# Controller.net
KiCad netlist of a schematic drawn in Altium Designer
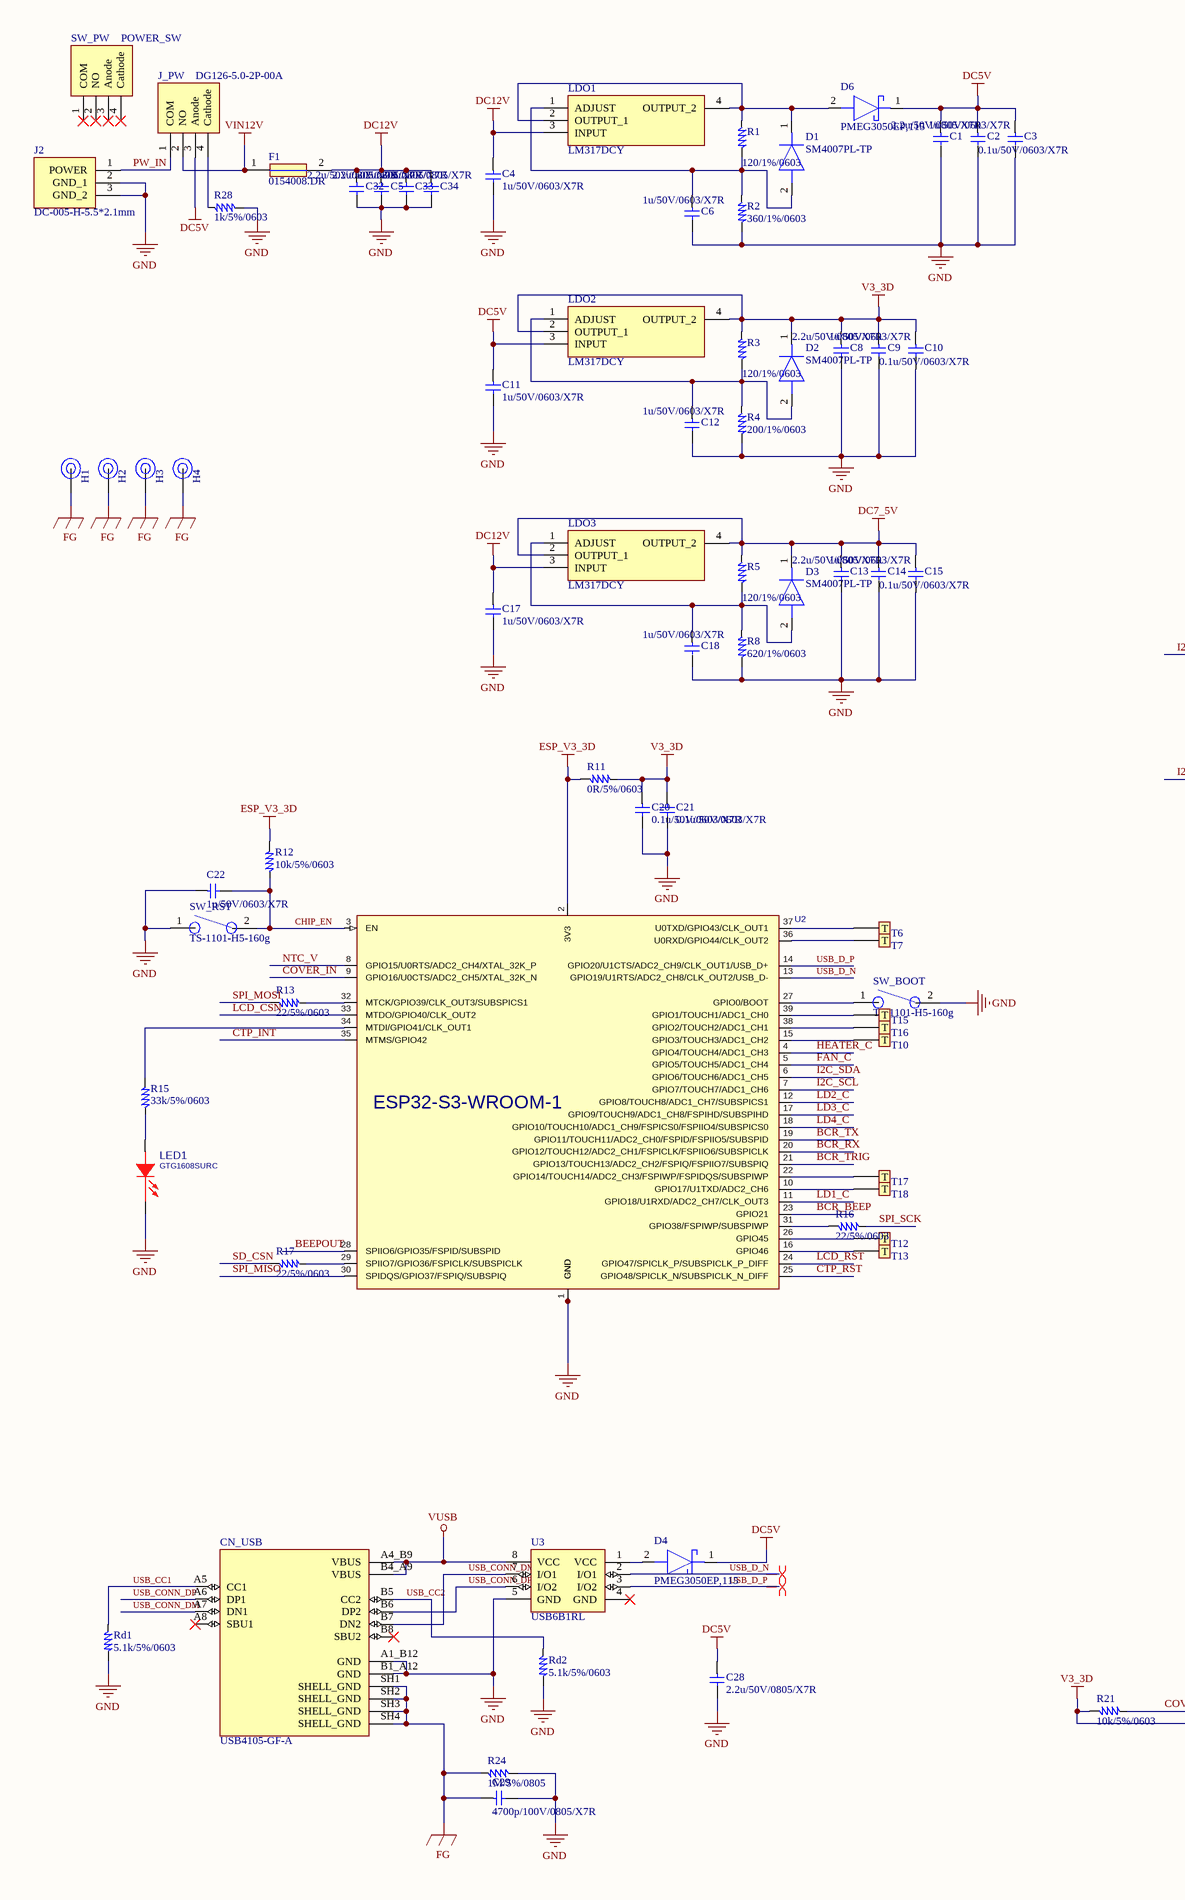
[diagram p0: Controller.SchDoc, left]
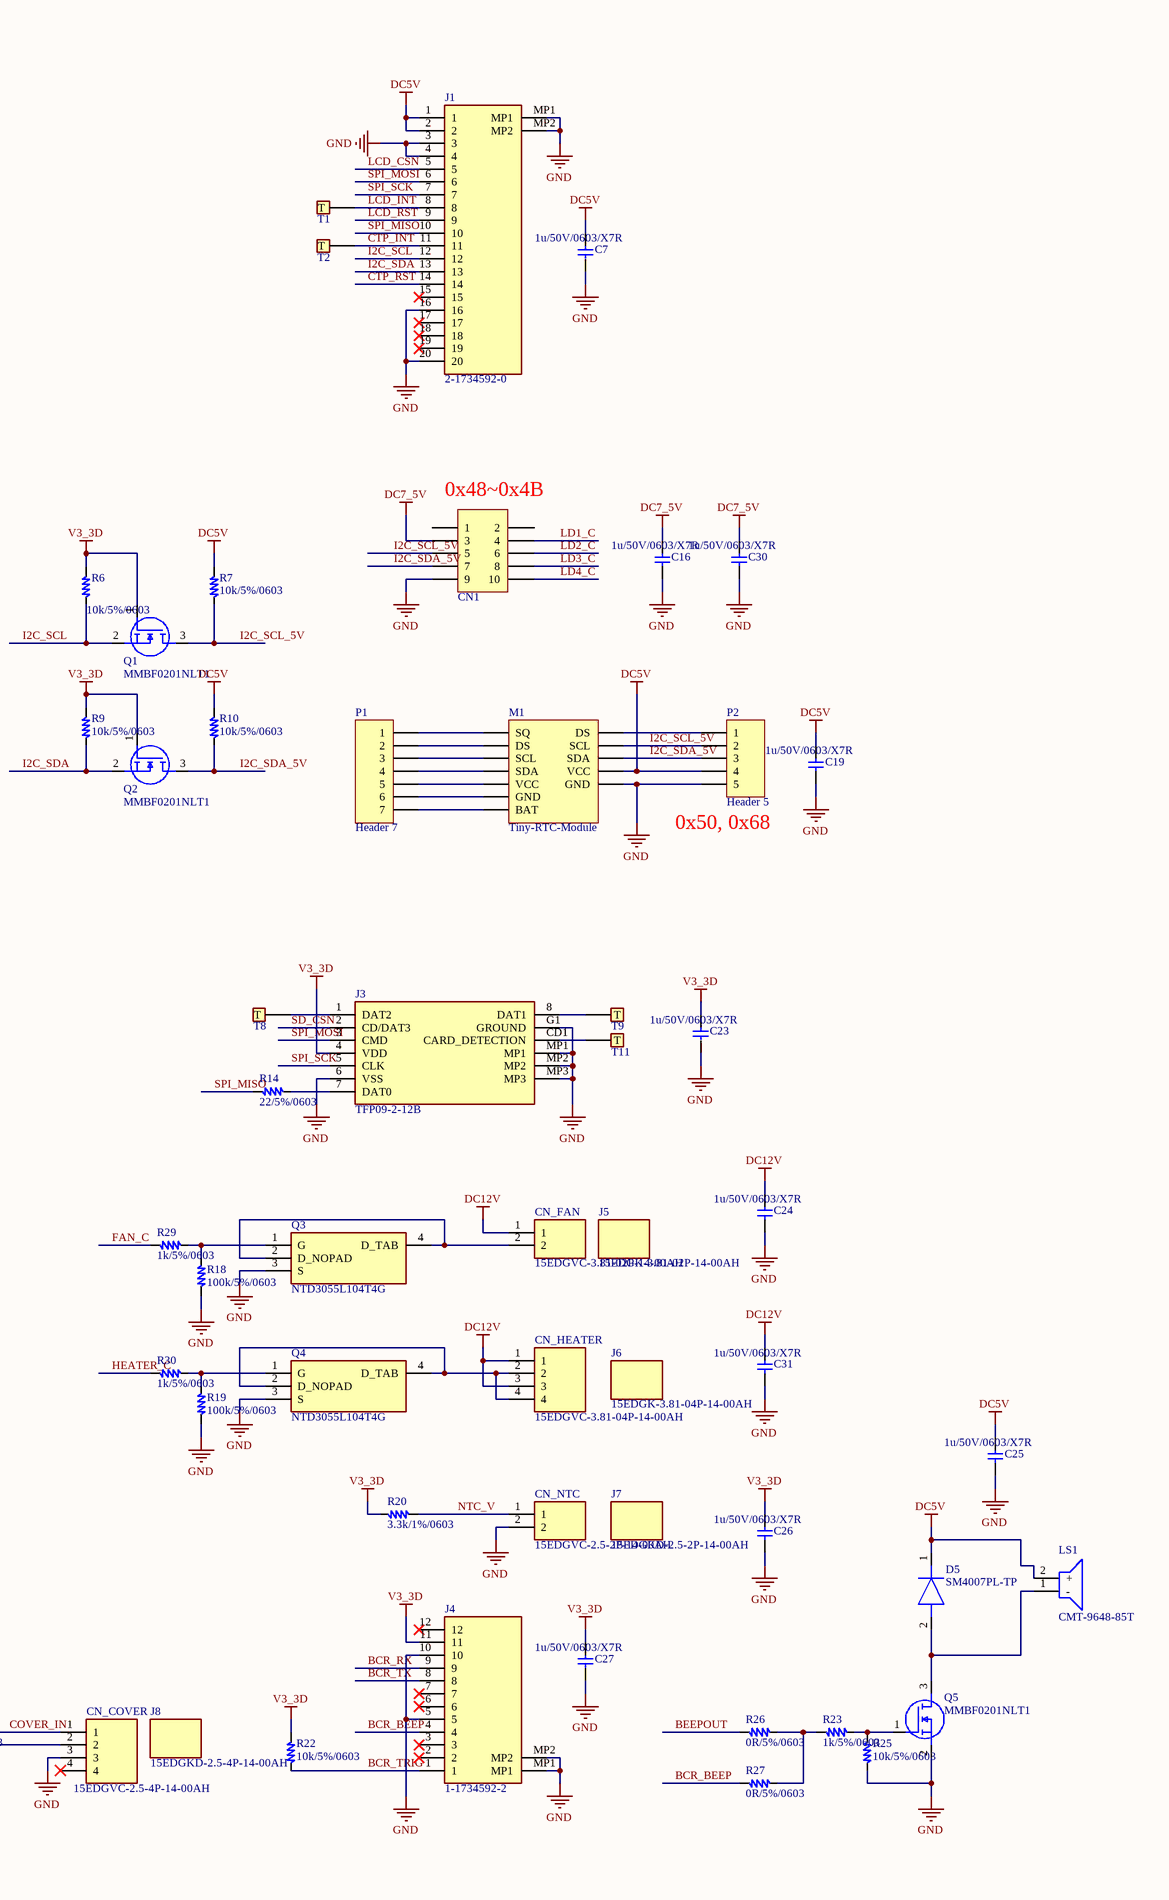
[diagram p1: Controller.SchDoc, right]

(export (version "E")
  (design (tool "Eeschema 10.0.6"))
  (components
    (comp (ref "C1")
      (value "2.2u/50V/0805/X7R")
      (footprint "CC0805")
      (description "CAP_MLCC")
      (libsource (lib "Biotaitan") (part "CAP_MLCC"))
    )
    (comp (ref "C2")
      (value "1u/50V/0603/X7R")
      (footprint "CC0603")
      (description "CAP_MLCC")
      (libsource (lib "Biotaitan") (part "CAP_MLCC"))
    )
    (comp (ref "C3")
      (value "0.1u/50V/0603/X7R")
      (footprint "CC0603")
      (description "CAP_MLCC")
      (libsource (lib "Biotaitan") (part "CAP_MLCC"))
    )
    (comp (ref "C4")
      (value "1u/50V/0603/X7R")
      (footprint "CC0603")
      (description "CAP_MLCC")
      (libsource (lib "Biotaitan") (part "CAP_MLCC"))
    )
    (comp (ref "C5")
      (value "2.2u/50V/0805/X7R")
      (footprint "CC0805")
      (description "CAP_MLCC")
      (libsource (lib "Biotaitan") (part "CAP_MLCC"))
    )
    (comp (ref "C6")
      (value "1u/50V/0603/X7R")
      (footprint "CC0603")
      (description "CAP_MLCC")
      (libsource (lib "Biotaitan") (part "CAP_MLCC"))
    )
    (comp (ref "C7")
      (value "1u/50V/0603/X7R")
      (footprint "CC0603")
      (description "CAP_MLCC")
      (libsource (lib "Biotaitan") (part "CAP_MLCC"))
    )
    (comp (ref "C8")
      (value "2.2u/50V/0805/X7R")
      (footprint "CC0805")
      (description "CAP_MLCC")
      (libsource (lib "Biotaitan") (part "CAP_MLCC"))
    )
    (comp (ref "C9")
      (value "1u/50V/0603/X7R")
      (footprint "CC0603")
      (description "CAP_MLCC")
      (libsource (lib "Biotaitan") (part "CAP_MLCC"))
    )
    (comp (ref "C10")
      (value "0.1u/50V/0603/X7R")
      (footprint "CC0603")
      (description "CAP_MLCC")
      (libsource (lib "Biotaitan") (part "CAP_MLCC"))
    )
    (comp (ref "C11")
      (value "1u/50V/0603/X7R")
      (footprint "CC0603")
      (description "CAP_MLCC")
      (libsource (lib "Biotaitan") (part "CAP_MLCC"))
    )
    (comp (ref "C12")
      (value "1u/50V/0603/X7R")
      (footprint "CC0603")
      (description "CAP_MLCC")
      (libsource (lib "Biotaitan") (part "CAP_MLCC"))
    )
    (comp (ref "C13")
      (value "2.2u/50V/0805/X7R")
      (footprint "CC0805")
      (description "CAP_MLCC")
      (libsource (lib "Biotaitan") (part "CAP_MLCC"))
    )
    (comp (ref "C14")
      (value "1u/50V/0603/X7R")
      (footprint "CC0603")
      (description "CAP_MLCC")
      (libsource (lib "Biotaitan") (part "CAP_MLCC"))
    )
    (comp (ref "C15")
      (value "0.1u/50V/0603/X7R")
      (footprint "CC0603")
      (description "CAP_MLCC")
      (libsource (lib "Biotaitan") (part "CAP_MLCC"))
    )
    (comp (ref "C16")
      (value "1u/50V/0603/X7R")
      (footprint "CC0603")
      (description "CAP_MLCC")
      (libsource (lib "Biotaitan") (part "CAP_MLCC"))
    )
    (comp (ref "C17")
      (value "1u/50V/0603/X7R")
      (footprint "CC0603")
      (description "CAP_MLCC")
      (libsource (lib "Biotaitan") (part "CAP_MLCC"))
    )
    (comp (ref "C18")
      (value "1u/50V/0603/X7R")
      (footprint "CC0603")
      (description "CAP_MLCC")
      (libsource (lib "Biotaitan") (part "CAP_MLCC"))
    )
    (comp (ref "C19")
      (value "1u/50V/0603/X7R")
      (footprint "CC0603")
      (description "CAP_MLCC")
      (libsource (lib "Biotaitan") (part "CAP_MLCC"))
    )
    (comp (ref "C20")
      (value "0.1u/50V/0603/X7R")
      (footprint "CC0603")
      (description "CAP_MLCC")
      (libsource (lib "Biotaitan") (part "CAP_MLCC"))
    )
    (comp (ref "C21")
      (value "0.1u/50V/0603/X7R")
      (footprint "CC0603")
      (description "CAP_MLCC")
      (libsource (lib "Biotaitan") (part "CAP_MLCC"))
    )
    (comp (ref "C22")
      (value "1u/50V/0603/X7R")
      (footprint "CC0603")
      (description "CAP_MLCC")
      (libsource (lib "Biotaitan") (part "CAP_MLCC"))
    )
    (comp (ref "C23")
      (value "1u/50V/0603/X7R")
      (footprint "CC0603")
      (description "CAP_MLCC")
      (libsource (lib "Biotaitan") (part "CAP_MLCC"))
    )
    (comp (ref "C24")
      (value "1u/50V/0603/X7R")
      (footprint "CC0603")
      (description "CAP_MLCC")
      (libsource (lib "Biotaitan") (part "CAP_MLCC"))
    )
    (comp (ref "C25")
      (value "1u/50V/0603/X7R")
      (footprint "CC0603")
      (description "CAP_MLCC")
      (libsource (lib "Biotaitan") (part "CAP_MLCC"))
    )
    (comp (ref "C26")
      (value "1u/50V/0603/X7R")
      (footprint "CC0603")
      (description "CAP_MLCC")
      (libsource (lib "Biotaitan") (part "CAP_MLCC"))
    )
    (comp (ref "C27")
      (value "1u/50V/0603/X7R")
      (footprint "CC0603")
      (description "CAP_MLCC")
      (libsource (lib "Biotaitan") (part "CAP_MLCC"))
    )
    (comp (ref "C28")
      (value "2.2u/50V/0805/X7R")
      (footprint "CC0805")
      (description "CAP_MLCC")
      (libsource (lib "Biotaitan") (part "CAP_MLCC"))
    )
    (comp (ref "C29")
      (value "4700p/100V/0805/X7R")
      (footprint "CC0805")
      (description "CAP_MLCC")
      (libsource (lib "Biotaitan") (part "CAP_MLCC"))
    )
    (comp (ref "C30")
      (value "1u/50V/0603/X7R")
      (footprint "CC0603")
      (description "CAP_MLCC")
      (libsource (lib "Biotaitan") (part "CAP_MLCC"))
    )
    (comp (ref "C31")
      (value "1u/50V/0603/X7R")
      (footprint "CC0603")
      (description "CAP_MLCC")
      (libsource (lib "Biotaitan") (part "CAP_MLCC"))
    )
    (comp (ref "C32")
      (value "2.2u/50V/0805/X7R")
      (footprint "CC0805")
      (description "CAP_MLCC")
      (libsource (lib "Biotaitan") (part "CAP_MLCC"))
    )
    (comp (ref "C33")
      (value "2.2u/50V/0805/X7R")
      (footprint "CC0805")
      (description "CAP_MLCC")
      (libsource (lib "Biotaitan") (part "CAP_MLCC"))
    )
    (comp (ref "C34")
      (value "2.2u/50V/0805/X7R")
      (footprint "CC0805")
      (description "CAP_MLCC")
      (libsource (lib "Biotaitan") (part "CAP_MLCC"))
    )
    (comp (ref "CN1")
      (value "320-10")
      (footprint "SHDR10W70P254_2X5_2000X850X900P")
      (description "IDC_(100y) VER TH 10POS 2.54MM")
      (libsource (lib "Biotaitan") (part "320-10"))
    )
    (comp (ref "CN_COVER")
      (value "15EDGVC-2.5-4P-14-00AH")
      (footprint "15EDGVC-2.5-4P-14-00AH")
      (description "端子台(百年)")
      (libsource (lib "Biotaitan") (part "15EDGVC-2.5-4P-14-00AH"))
    )
    (comp (ref "CN_FAN")
      (value "15EDGVC-3.81-02P-14-00AH")
      (footprint "15EDGVC-3.81-02P-14-00AH")
      (description "端子台(百年)")
      (libsource (lib "Biotaitan") (part "15EDGVC-3.81-02P-14-00AH"))
    )
    (comp (ref "CN_HEATER")
      (value "15EDGVC-3.81-04P-14-00AH")
      (footprint "15EDGVC-3.81-04P-14-00AH")
      (description "端子台(百年)")
      (libsource (lib "Biotaitan") (part "15EDGVC-3.81-04P-14-00AH"))
    )
    (comp (ref "CN_NTC")
      (value "15EDGVC-2.5-2P-14-00AH")
      (footprint "15EDGVC-2.5-2P-14-00AH")
      (description "端子台(百年)")
      (libsource (lib "Biotaitan") (part "15EDGVC-2.5-2P-14-00AH"))
    )
    (comp (ref "CN_USB")
      (value "USB4105-GF-A")
      (footprint "USB4105-GF-A")
      (description "USB_Type-C (USB2.0) 24P(16+8 Dummy)  SMD RA")
      (libsource (lib "Biotaitan") (part "USB4105-GF-A"))
    )
    (comp (ref "D1")
      (value "SM4007PL-TP")
      (footprint "SM4007PLTP")
      (description "整流器 1A, 1000V 1A, 1000V")
      (libsource (lib "Biotaitan") (part "SM4007PL-TP"))
    )
    (comp (ref "D2")
      (value "SM4007PL-TP")
      (footprint "SM4007PLTP")
      (description "整流器 1A, 1000V 1A, 1000V")
      (libsource (lib "Biotaitan") (part "SM4007PL-TP"))
    )
    (comp (ref "D3")
      (value "SM4007PL-TP")
      (footprint "SM4007PLTP")
      (description "整流器 1A, 1000V 1A, 1000V")
      (libsource (lib "Biotaitan") (part "SM4007PL-TP"))
    )
    (comp (ref "D4")
      (value "PMEG3050EP,115")
      (footprint "PMEG3050EP115")
      (description "Schottky_RECT 30V 5A VF 0.315V")
      (libsource (lib "Biotaitan") (part "PMEG3050EP,115"))
    )
    (comp (ref "D5")
      (value "SM4007PL-TP")
      (footprint "SM4007PLTP")
      (description "整流器 1A, 1000V 1A, 1000V")
      (libsource (lib "Biotaitan") (part "SM4007PL-TP"))
    )
    (comp (ref "D6")
      (value "PMEG3050EP,115")
      (footprint "PMEG3050EP115")
      (description "Schottky_RECT 30V 5A VF 0.315V")
      (libsource (lib "Biotaitan") (part "PMEG3050EP,115"))
    )
    (comp (ref "F1")
      (value "0154008.DR")
      (footprint "0154001.DRT")
      (description "Fuse")
      (libsource (lib "Biotaitan") (part "0154008.DR"))
    )
    (comp (ref "H1")
      (value "Screw_holes_3p5mm")
      (footprint "Screw_holes_3p5mm")
      (description "Screw holes")
      (libsource (lib "Biotaitan") (part "Screw_holes"))
    )
    (comp (ref "H2")
      (value "Screw_holes_3p5mm")
      (footprint "Screw_holes_3p5mm")
      (description "Screw holes")
      (libsource (lib "Biotaitan") (part "Screw_holes"))
    )
    (comp (ref "H3")
      (value "Screw_holes_3p5mm")
      (footprint "Screw_holes_3p5mm")
      (description "Screw holes")
      (libsource (lib "Biotaitan") (part "Screw_holes"))
    )
    (comp (ref "H4")
      (value "Screw_holes_3p5mm")
      (footprint "Screw_holes_3p5mm")
      (description "Screw holes")
      (libsource (lib "Biotaitan") (part "Screw_holes"))
    )
    (comp (ref "J1")
      (value "2-1734592-0")
      (footprint "217345920")
      (description "FFC和FPC連接器 0.5mm PITCH B/C 20P")
      (libsource (lib "Biotaitan") (part "2-1734592-0"))
    )
    (comp (ref "J2")
      (value "DC-005-H-5.5*2.1mm")
      (footprint "DC-005-H-5.5*2.1mm")
      (description "DC-005-H-5.5*2.1mm(百年)")
      (libsource (lib "Biotaitan") (part "DC-005-H-5.5*2.1mm"))
    )
    (comp (ref "J3")
      (value "TFP09-2-12B")
      (footprint "TFP09212B")
      (description "Micro SD Card Connector(百年)")
      (libsource (lib "Biotaitan") (part "TFP09-2-12B"))
    )
    (comp (ref "J4")
      (value "1-1734592-2")
      (footprint "117345922")
      (description "FFC和FPC連接器 0.5mm PITCH B/C 12P")
      (libsource (lib "Biotaitan") (part "1-1734592-2"))
    )
    (comp (ref "J5")
      (value "15EDGK-3.81-02P-14-00AH")
      (footprint "15EDGK-3.81-02P-14-00AH")
      (description "端子接頭(百年)")
      (libsource (lib "Biotaitan") (part "15EDGK-3.81-02P-14-00AH"))
    )
    (comp (ref "J6")
      (value "15EDGK-3.81-04P-14-00AH")
      (footprint "15EDGK-3.81-04P-14-00AH")
      (description "端子接頭(百年)")
      (libsource (lib "Biotaitan") (part "15EDGK-3.81-04P-14-00AH"))
    )
    (comp (ref "J7")
      (value "15EDGKD-2.5-2P-14-00AH")
      (footprint "15EDGKD-2.5-2P-14-00AH")
      (description "端子接頭(百年)")
      (libsource (lib "Biotaitan") (part "15EDGKD-2.5-2P-14-00AH"))
    )
    (comp (ref "J8")
      (value "15EDGKD-2.5-4P-14-00AH")
      (footprint "15EDGKD-2.5-4P-14-00AH")
      (description "端子接頭(百年)")
      (libsource (lib "Biotaitan") (part "15EDGKD-2.5-4P-14-00AH"))
    )
    (comp (ref "J_PW")
      (value "DG126-5.0-2P-00A")
      (footprint "DG126-5.0-2P-00A_PW_SW")
      (description "端子台")
      (libsource (lib "Biotaitan") (part "DG126-5.0-2P-00A_SW"))
    )
    (comp (ref "LDO1")
      (value "LM317DCY")
      (footprint "SOT230P700X180-4N")
      (description "線性電壓穩壓器 3 T 1.5A Adj Pos V")
      (libsource (lib "Biotaitan") (part "LM317DCY"))
    )
    (comp (ref "LDO2")
      (value "LM317DCY")
      (footprint "SOT230P700X180-4N")
      (description "線性電壓穩壓器 3 T 1.5A Adj Pos V")
      (libsource (lib "Biotaitan") (part "LM317DCY"))
    )
    (comp (ref "LDO3")
      (value "LM317DCY")
      (footprint "SOT230P700X180-4N")
      (description "線性電壓穩壓器 3 T 1.5A Adj Pos V")
      (libsource (lib "Biotaitan") (part "LM317DCY"))
    )
    (comp (ref "LED1")
      (value "GTG1608SURC")
      (footprint "LED0603_RED")
      (description "LED0603_RED(百年)")
      (libsource (lib "Biotaitan") (part "GTG1608SURC"))
    )
    (comp (ref "LS1")
      (value "CMT-9648-85T")
      (footprint "CMT964885T")
      (description "Loudspeaker or Buzzer")
      (libsource (lib "Biotaitan") (part "CMT-9648-85T"))
    )
    (comp (ref "M1")
      (value "Tiny-RTC-Module")
      (footprint "TINY RTC I2C Module")
      (description "DS1307 RTC Module\r\n(百年)100698")
      (libsource (lib "Biotaitan") (part "Tiny-RTC-Module"))
    )
    (comp (ref "P1")
      (value "Header 7")
      (footprint "HDR1X7_2.54_ST_H8.54")
      (description "D15-40P/全長-14.2MM(百年)")
      (libsource (lib "Biotaitan") (part "Header 7"))
    )
    (comp (ref "P2")
      (value "Header 5")
      (footprint "HDR1X5_2.54_ST_H8.54")
      (description "D15-40P/全長-14.2MM(百年)")
      (libsource (lib "Biotaitan") (part "Header 5"))
    )
    (comp (ref "Q1")
      (value "MMBF0201NLT1")
      (footprint "SOT65P210X110-3N")
      (description "MOSFET (N-Channel)(百年)")
      (libsource (lib "Biotaitan") (part "MMBF0201NLT1"))
    )
    (comp (ref "Q2")
      (value "MMBF0201NLT1")
      (footprint "SOT65P210X110-3N")
      (description "MOSFET (N-Channel)(百年)")
      (libsource (lib "Biotaitan") (part "MMBF0201NLT1"))
    )
    (comp (ref "Q3")
      (value "NTD3055L104T4G")
      (footprint "TO229P990X238-4N")
      (description "MOSFET 60V 12A N-Channel")
      (libsource (lib "Biotaitan") (part "NTD3055L104T4G"))
    )
    (comp (ref "Q4")
      (value "NTD3055L104T4G")
      (footprint "TO229P990X238-4N")
      (description "MOSFET 60V 12A N-Channel")
      (libsource (lib "Biotaitan") (part "NTD3055L104T4G"))
    )
    (comp (ref "Q5")
      (value "MMBF0201NLT1")
      (footprint "SOT65P210X110-3N")
      (description "MOSFET (N-Channel)(百年)")
      (libsource (lib "Biotaitan") (part "MMBF0201NLT1"))
    )
    (comp (ref "R1")
      (value "120/1%/0603")
      (footprint "CC0603_R")
      (description "RES_")
      (libsource (lib "Biotaitan") (part "RES_SMD"))
    )
    (comp (ref "R2")
      (value "360/1%/0603")
      (footprint "CC0603_R")
      (description "RES_")
      (libsource (lib "Biotaitan") (part "RES_SMD"))
    )
    (comp (ref "R3")
      (value "120/1%/0603")
      (footprint "CC0603_R")
      (description "RES_")
      (libsource (lib "Biotaitan") (part "RES_SMD"))
    )
    (comp (ref "R4")
      (value "200/1%/0603")
      (footprint "CC0603_R")
      (description "RES_")
      (libsource (lib "Biotaitan") (part "RES_SMD"))
    )
    (comp (ref "R5")
      (value "120/1%/0603")
      (footprint "CC0603_R")
      (description "RES_")
      (libsource (lib "Biotaitan") (part "RES_SMD"))
    )
    (comp (ref "R6")
      (value "10k/5%/0603")
      (footprint "CC0603_R")
      (description "RES_")
      (libsource (lib "Biotaitan") (part "RES_SMD"))
    )
    (comp (ref "R7")
      (value "10k/5%/0603")
      (footprint "CC0603_R")
      (description "RES_")
      (libsource (lib "Biotaitan") (part "RES_SMD"))
    )
    (comp (ref "R8")
      (value "620/1%/0603")
      (footprint "CC0603_R")
      (description "RES_")
      (libsource (lib "Biotaitan") (part "RES_SMD"))
    )
    (comp (ref "R9")
      (value "10k/5%/0603")
      (footprint "CC0603_R")
      (description "RES_")
      (libsource (lib "Biotaitan") (part "RES_SMD"))
    )
    (comp (ref "R10")
      (value "10k/5%/0603")
      (footprint "CC0603_R")
      (description "RES_")
      (libsource (lib "Biotaitan") (part "RES_SMD"))
    )
    (comp (ref "R11")
      (value "0R/5%/0603")
      (footprint "CC0603_R")
      (description "RES_")
      (libsource (lib "Biotaitan") (part "RES_SMD"))
    )
    (comp (ref "R12")
      (value "10k/5%/0603")
      (footprint "CC0603_R")
      (description "RES_")
      (libsource (lib "Biotaitan") (part "RES_SMD"))
    )
    (comp (ref "R13")
      (value "22/5%/0603")
      (footprint "CC0603_R")
      (description "RES_")
      (libsource (lib "Biotaitan") (part "RES_SMD"))
    )
    (comp (ref "R14")
      (value "22/5%/0603")
      (footprint "CC0603_R")
      (description "RES_")
      (libsource (lib "Biotaitan") (part "RES_SMD"))
    )
    (comp (ref "R15")
      (value "33k/5%/0603")
      (footprint "CC0603_R")
      (description "RES_")
      (libsource (lib "Biotaitan") (part "RES_SMD"))
    )
    (comp (ref "R16")
      (value "22/5%/0603")
      (footprint "CC0603_R")
      (description "RES_")
      (libsource (lib "Biotaitan") (part "RES_SMD"))
    )
    (comp (ref "R17")
      (value "22/5%/0603")
      (footprint "CC0603_R")
      (description "RES_")
      (libsource (lib "Biotaitan") (part "RES_SMD"))
    )
    (comp (ref "R18")
      (value "100k/5%/0603")
      (footprint "CC0603_R")
      (description "RES_")
      (libsource (lib "Biotaitan") (part "RES_SMD"))
    )
    (comp (ref "R19")
      (value "100k/5%/0603")
      (footprint "CC0603_R")
      (description "RES_")
      (libsource (lib "Biotaitan") (part "RES_SMD"))
    )
    (comp (ref "R20")
      (value "3.3k/1%/0603")
      (footprint "CC0603_R")
      (description "RES_")
      (libsource (lib "Biotaitan") (part "RES_SMD"))
    )
    (comp (ref "R21")
      (value "10k/5%/0603")
      (footprint "CC0603_R")
      (description "RES_")
      (libsource (lib "Biotaitan") (part "RES_SMD"))
    )
    (comp (ref "R22")
      (value "10k/5%/0603")
      (footprint "CC0603_R")
      (description "RES_")
      (libsource (lib "Biotaitan") (part "RES_SMD"))
    )
    (comp (ref "R23")
      (value "1k/5%/0603")
      (footprint "CC0603_R")
      (description "RES_")
      (libsource (lib "Biotaitan") (part "RES_SMD"))
    )
    (comp (ref "R24")
      (value "1M/5%/0805")
      (footprint "CC0805_R")
      (description "RES_")
      (libsource (lib "Biotaitan") (part "RES_SMD"))
    )
    (comp (ref "R25")
      (value "10k/5%/0603")
      (footprint "CC0603_R")
      (description "RES_")
      (libsource (lib "Biotaitan") (part "RES_SMD"))
    )
    (comp (ref "R26")
      (value "0R/5%/0603")
      (footprint "CC0603_R")
      (description "RES_")
      (libsource (lib "Biotaitan") (part "RES_SMD"))
    )
    (comp (ref "R27")
      (value "0R/5%/0603")
      (footprint "CC0603_R")
      (description "RES_")
      (libsource (lib "Biotaitan") (part "RES_SMD"))
    )
    (comp (ref "R28")
      (value "1k/5%/0603")
      (footprint "CC0603_R")
      (description "RES_")
      (libsource (lib "Biotaitan") (part "RES_SMD"))
    )
    (comp (ref "R29")
      (value "1k/5%/0603")
      (footprint "CC0603_R")
      (description "RES_")
      (libsource (lib "Biotaitan") (part "RES_SMD"))
    )
    (comp (ref "R30")
      (value "1k/5%/0603")
      (footprint "CC0603_R")
      (description "RES_")
      (libsource (lib "Biotaitan") (part "RES_SMD"))
    )
    (comp (ref "Rd1")
      (value "5.1k/5%/0603")
      (footprint "CC0603_R")
      (description "RES_")
      (libsource (lib "Biotaitan") (part "RES_SMD"))
    )
    (comp (ref "Rd2")
      (value "5.1k/5%/0603")
      (footprint "CC0603_R")
      (description "RES_")
      (libsource (lib "Biotaitan") (part "RES_SMD"))
    )
    (comp (ref "SW_BOOT")
      (value "TS-1101-H5-160g")
      (footprint "TS-1101-H5-160g")
      (description "Switch_Tact Switch\r\nTS-1101-H5-160g(百年)")
      (libsource (lib "Biotaitan") (part "TS-1101-H5-160g"))
    )
    (comp (ref "SW_PW")
      (value "POWER_SW")
      (footprint "POWER_SW")
      (description "帶燈Switch")
      (libsource (lib "Biotaitan") (part "POWER_SW"))
    )
    (comp (ref "SW_RST")
      (value "TS-1101-H5-160g")
      (footprint "TS-1101-H5-160g")
      (description "Switch_Tact Switch\r\nTS-1101-H5-160g(百年)")
      (libsource (lib "Biotaitan") (part "TS-1101-H5-160g"))
    )
    (comp (ref "T1") (value "Test_Pad") (footprint "Test_Pad_40mil") (libsource (lib "") (part "Test_Pad_1")))
    (comp (ref "T2") (value "Test_Pad") (footprint "Test_Pad_40mil") (libsource (lib "") (part "Test_Pad_1")))
    (comp (ref "T6")
      (value "Test_Pad")
      (footprint "Test_Pad_40mil")
      (libsource (lib "Biotaitan") (part "Test_Pad"))
    )
    (comp (ref "T7")
      (value "Test_Pad")
      (footprint "Test_Pad_40mil")
      (libsource (lib "Biotaitan") (part "Test_Pad"))
    )
    (comp (ref "T8") (value "Test_Pad") (footprint "Test_Pad_40mil") (libsource (lib "") (part "Test_Pad_1")))
    (comp (ref "T9")
      (value "Test_Pad")
      (footprint "Test_Pad_40mil")
      (libsource (lib "Biotaitan") (part "Test_Pad"))
    )
    (comp (ref "T10")
      (value "Test_Pad")
      (footprint "Test_Pad_40mil")
      (libsource (lib "Biotaitan") (part "Test_Pad"))
    )
    (comp (ref "T11")
      (value "Test_Pad")
      (footprint "Test_Pad_40mil")
      (libsource (lib "Biotaitan") (part "Test_Pad"))
    )
    (comp (ref "T12")
      (value "Test_Pad")
      (footprint "Test_Pad_40mil")
      (libsource (lib "Biotaitan") (part "Test_Pad"))
    )
    (comp (ref "T13")
      (value "Test_Pad")
      (footprint "Test_Pad_40mil")
      (libsource (lib "Biotaitan") (part "Test_Pad"))
    )
    (comp (ref "T15")
      (value "Test_Pad")
      (footprint "Test_Pad_40mil")
      (libsource (lib "Biotaitan") (part "Test_Pad"))
    )
    (comp (ref "T16")
      (value "Test_Pad")
      (footprint "Test_Pad_40mil")
      (libsource (lib "Biotaitan") (part "Test_Pad"))
    )
    (comp (ref "T17")
      (value "Test_Pad")
      (footprint "Test_Pad_40mil")
      (libsource (lib "Biotaitan") (part "Test_Pad"))
    )
    (comp (ref "T18")
      (value "Test_Pad")
      (footprint "Test_Pad_40mil")
      (libsource (lib "Biotaitan") (part "Test_Pad"))
    )
    (comp (ref "U2")
      (value "ESP32-S3-WROOM-1-N8R2")
      (footprint "ESP32S3WROOM1N8R2")
      (description "MCU_ESP32-S3 8M Flash 2MB SRAM with PCB Antenan")
      (libsource (lib "Biotaitan") (part "ESP32-S3-WROOM-1"))
    )
    (comp (ref "U3")
      (value "USB6B1RL")
      (footprint "SOIC127P600X175-8N")
      (description "TVS_6V 25A/ ESD_2-Channel +/-8kV")
      (libsource (lib "Biotaitan") (part "USB6B1RL"))
    )
  )
  (nets
    (net (code "1") (name "/BCR_BEEP") (class "Default")
      (node (ref "J4") (pin "4") (pinfunction "4_4") (pintype "passive"))
      (node (ref "R27") (pin "2") (pinfunction "2_2") (pintype "passive"))
      (node (ref "U2") (pin "23") (pinfunction "GPIO21_23") (pintype "bidirectional"))
    )
    (net (code "2") (name "/BCR_RX") (class "Default")
      (node (ref "J4") (pin "9") (pinfunction "9_9") (pintype "passive"))
      (node (ref "U2") (pin "20") (pinfunction "GPIO12/TOUCH12/ADC2_CH1/FSPICLK/FSPIIO6/SUBSPICLK_20") (pintype "bidirectional"))
    )
    (net (code "3") (name "/BCR_TRIG") (class "Default")
      (node (ref "J4") (pin "1") (pinfunction "1_1") (pintype "passive"))
      (node (ref "R22") (pin "1") (pinfunction "1_1") (pintype "passive"))
      (node (ref "U2") (pin "21") (pinfunction "GPIO13/TOUCH13/ADC2_CH2/FSPIQ/FSPIIO7/SUBSPIQ_21") (pintype "bidirectional"))
    )
    (net (code "4") (name "/BCR_TX") (class "Default")
      (node (ref "J4") (pin "8") (pinfunction "8_8") (pintype "passive"))
      (node (ref "U2") (pin "19") (pinfunction "GPIO11/TOUCH11/ADC2_CH0/FSPID/FSPIIO5/SUBSPID_19") (pintype "bidirectional"))
    )
    (net (code "5") (name "/BEEPOUT") (class "Default")
      (node (ref "R26") (pin "2") (pinfunction "2_2") (pintype "passive"))
      (node (ref "U2") (pin "28") (pinfunction "SPIIO6/GPIO35/FSPID/SUBSPID_28") (pintype "bidirectional"))
    )
    (net (code "6") (name "/CHIP_EN") (class "Default")
      (node (ref "C22") (pin "2") (pinfunction "2_2") (pintype "passive"))
      (node (ref "R12") (pin "1") (pinfunction "1_1") (pintype "passive"))
      (node (ref "SW_RST") (pin "2") (pinfunction "NO_1_2") (pintype "passive"))
      (node (ref "U2") (pin "3") (pinfunction "EN_3") (pintype "input"))
    )
    (net (code "7") (name "/COVER_IN") (class "Default")
      (node (ref "CN_COVER") (pin "1") (pinfunction "1_1") (pintype "passive"))
      (node (ref "R21") (pin "1") (pinfunction "1_1") (pintype "passive"))
      (node (ref "U2") (pin "9") (pinfunction "GPIO16/U0CTS/ADC2_CH5/XTAL_32K_N_9") (pintype "bidirectional"))
    )
    (net (code "8") (name "/CTP_INT") (class "Default")
      (node (ref "J1") (pin "11") (pinfunction "11_11") (pintype "passive"))
      (node (ref "T2") (pin "1") (pinfunction "T_1") (pintype "passive"))
      (node (ref "U2") (pin "35") (pinfunction "MTMS/GPIO42_35") (pintype "bidirectional"))
    )
    (net (code "9") (name "/CTP_RST") (class "Default")
      (node (ref "J1") (pin "14") (pinfunction "14_14") (pintype "passive"))
      (node (ref "U2") (pin "25") (pinfunction "GPIO48/SPICLK_N/SUBSPICLK_N_DIFF_25") (pintype "bidirectional"))
    )
    (net (code "10") (name "/FAN_C") (class "Default")
      (node (ref "R29") (pin "2") (pinfunction "2_2") (pintype "passive"))
      (node (ref "U2") (pin "5") (pinfunction "GPIO5/TOUCH5/ADC1_CH4_5") (pintype "bidirectional"))
    )
    (net (code "11") (name "/HEATER_C") (class "Default")
      (node (ref "R30") (pin "2") (pinfunction "2_2") (pintype "passive"))
      (node (ref "U2") (pin "4") (pinfunction "GPIO4/TOUCH4/ADC1_CH3_4") (pintype "bidirectional"))
    )
    (net (code "12") (name "/I2C_SCL") (class "Default")
      (node (ref "J1") (pin "12") (pinfunction "12_12") (pintype "passive"))
      (node (ref "Q1") (pin "2") (pinfunction "S_2") (pintype "passive"))
      (node (ref "R6") (pin "1") (pinfunction "1_1") (pintype "passive"))
      (node (ref "U2") (pin "7") (pinfunction "GPIO7/TOUCH7/ADC1_CH6_7") (pintype "bidirectional"))
    )
    (net (code "13") (name "/I2C_SCL_5V") (class "Default")
      (node (ref "CN1") (pin "5") (pinfunction "5_5") (pintype "passive"))
      (node (ref "M1") (pin "11") (pinfunction "SCL_11") (pintype "passive"))
      (node (ref "P2") (pin "2") (pinfunction "2_2") (pintype "passive"))
      (node (ref "Q1") (pin "3") (pinfunction "D_3") (pintype "passive"))
      (node (ref "R7") (pin "1") (pinfunction "1_1") (pintype "passive"))
    )
    (net (code "14") (name "/I2C_SDA") (class "Default")
      (node (ref "J1") (pin "13") (pinfunction "13_13") (pintype "passive"))
      (node (ref "Q2") (pin "2") (pinfunction "S_2") (pintype "passive"))
      (node (ref "R9") (pin "1") (pinfunction "1_1") (pintype "passive"))
      (node (ref "U2") (pin "6") (pinfunction "GPIO6/TOUCH6/ADC1_CH5_6") (pintype "bidirectional"))
    )
    (net (code "15") (name "/I2C_SDA_5V") (class "Default")
      (node (ref "CN1") (pin "7") (pinfunction "7_7") (pintype "passive"))
      (node (ref "M1") (pin "10") (pinfunction "SDA_10") (pintype "passive"))
      (node (ref "P2") (pin "3") (pinfunction "3_3") (pintype "passive"))
      (node (ref "Q2") (pin "3") (pinfunction "D_3") (pintype "passive"))
      (node (ref "R10") (pin "1") (pinfunction "1_1") (pintype "passive"))
    )
    (net (code "16") (name "/LCD_CSN") (class "Default")
      (node (ref "J1") (pin "5") (pinfunction "5_5") (pintype "passive"))
      (node (ref "U2") (pin "33") (pinfunction "MTDO/GPIO40/CLK_OUT2_33") (pintype "bidirectional"))
    )
    (net (code "17") (name "/LCD_INT") (class "Default")
      (node (ref "J1") (pin "8") (pinfunction "8_8") (pintype "passive"))
      (node (ref "T1") (pin "1") (pinfunction "T_1") (pintype "passive"))
    )
    (net (code "18") (name "/LCD_RST") (class "Default")
      (node (ref "J1") (pin "9") (pinfunction "9_9") (pintype "passive"))
      (node (ref "U2") (pin "24") (pinfunction "GPIO47/SPICLK_P/SUBSPICLK_P_DIFF_24") (pintype "bidirectional"))
    )
    (net (code "19") (name "/LD1_C") (class "Default")
      (node (ref "CN1") (pin "4") (pinfunction "4_4") (pintype "passive"))
      (node (ref "U2") (pin "11") (pinfunction "GPIO18/U1RXD/ADC2_CH7/CLK_OUT3_11") (pintype "bidirectional"))
    )
    (net (code "20") (name "/LD2_C") (class "Default")
      (node (ref "CN1") (pin "6") (pinfunction "6_6") (pintype "passive"))
      (node (ref "U2") (pin "12") (pinfunction "GPIO8/TOUCH8/ADC1_CH7/SUBSPICS1_12") (pintype "bidirectional"))
    )
    (net (code "21") (name "/LD3_C") (class "Default")
      (node (ref "CN1") (pin "8") (pinfunction "8_8") (pintype "passive"))
      (node (ref "U2") (pin "17") (pinfunction "GPIO9/TOUCH9/ADC1_CH8/FSPIHD/SUBSPIHD_17") (pintype "bidirectional"))
    )
    (net (code "22") (name "/LD4_C") (class "Default")
      (node (ref "CN1") (pin "10") (pinfunction "10_10") (pintype "passive"))
      (node (ref "U2") (pin "18") (pinfunction "GPIO10/TOUCH10/ADC1_CH9/FSPICS0/FSPIIO4/SUBSPICS0_18") (pintype "bidirectional"))
    )
    (net (code "23") (name "/NTC_V") (class "Default")
      (node (ref "CN_NTC") (pin "1") (pinfunction "1_1") (pintype "passive"))
      (node (ref "R20") (pin "2") (pinfunction "2_2") (pintype "passive"))
      (node (ref "U2") (pin "8") (pinfunction "GPIO15/U0RTS/ADC2_CH4/XTAL_32K_P_8") (pintype "bidirectional"))
    )
    (net (code "24") (name "/PW_IN") (class "Default")
      (node (ref "J2") (pin "1") (pinfunction "POWER_1") (pintype "passive"))
      (node (ref "J_PW") (pin "1") (pinfunction "COM_1") (pintype "passive"))
    )
    (net (code "25") (name "/SD_CSN") (class "Default")
      (node (ref "J3") (pin "2") (pinfunction "CD/DAT3_2") (pintype "passive"))
      (node (ref "R17") (pin "2") (pinfunction "2_2") (pintype "passive"))
    )
    (net (code "26") (name "/SPI_MISO") (class "Default")
      (node (ref "J1") (pin "10") (pinfunction "10_10") (pintype "passive"))
      (node (ref "R14") (pin "2") (pinfunction "2_2") (pintype "passive"))
      (node (ref "U2") (pin "30") (pinfunction "SPIDQS/GPIO37/FSPIQ/SUBSPIQ_30") (pintype "bidirectional"))
    )
    (net (code "27") (name "/SPI_MOSI") (class "Default")
      (node (ref "J1") (pin "6") (pinfunction "6_6") (pintype "passive"))
      (node (ref "J3") (pin "3") (pinfunction "CMD_3") (pintype "passive"))
      (node (ref "R13") (pin "2") (pinfunction "2_2") (pintype "passive"))
    )
    (net (code "28") (name "/SPI_SCK") (class "Default")
      (node (ref "J1") (pin "7") (pinfunction "7_7") (pintype "passive"))
      (node (ref "J3") (pin "5") (pinfunction "CLK_5") (pintype "passive"))
      (node (ref "R16") (pin "1") (pinfunction "1_1") (pintype "passive"))
    )
    (net (code "29") (name "/USB_CC1") (class "Default")
      (node (ref "CN_USB") (pin "A5") (pinfunction "CC1_A5") (pintype "bidirectional"))
      (node (ref "Rd1") (pin "1") (pinfunction "1_1") (pintype "passive"))
    )
    (net (code "30") (name "/USB_CC2") (class "Default")
      (node (ref "CN_USB") (pin "B5") (pinfunction "CC2_B5") (pintype "bidirectional"))
      (node (ref "Rd2") (pin "1") (pinfunction "1_1") (pintype "passive"))
    )
    (net (code "31") (name "/USB_CONN_DM") (class "Default")
      (node (ref "CN_USB") (pin "A7") (pinfunction "DN1_A7") (pintype "bidirectional"))
      (node (ref "CN_USB") (pin "B7") (pinfunction "DN2_B7") (pintype "bidirectional"))
      (node (ref "U3") (pin "7") (pinfunction "I/O1_7") (pintype "bidirectional"))
    )
    (net (code "32") (name "/USB_CONN_DP") (class "Default")
      (node (ref "CN_USB") (pin "A6") (pinfunction "DP1_A6") (pintype "bidirectional"))
      (node (ref "CN_USB") (pin "B6") (pinfunction "DP2_B6") (pintype "bidirectional"))
      (node (ref "U3") (pin "6") (pinfunction "I/O2_6") (pintype "bidirectional"))
    )
    (net (code "33") (name "/USB_D_N") (class "Default")
      (node (ref "U2") (pin "13") (pinfunction "GPIO19/U1RTS/ADC2_CH8/CLK_OUT2/USB_D-_13") (pintype "bidirectional"))
      (node (ref "U3") (pin "2") (pinfunction "I/O1_2") (pintype "bidirectional"))
    )
    (net (code "34") (name "/USB_D_P") (class "Default")
      (node (ref "U2") (pin "14") (pinfunction "GPIO20/U1CTS/ADC2_CH9/CLK_OUT1/USB_D+_14") (pintype "bidirectional"))
      (node (ref "U3") (pin "3") (pinfunction "I/O2_3") (pintype "bidirectional"))
    )
    (net (code "35") (name "DC5V") (class "Default")
      (node (ref "C1") (pin "1") (pinfunction "1_1") (pintype "passive"))
      (node (ref "C11") (pin "1") (pinfunction "1_1") (pintype "passive"))
      (node (ref "C19") (pin "1") (pinfunction "1_1") (pintype "passive"))
      (node (ref "C2") (pin "1") (pinfunction "1_1") (pintype "passive"))
      (node (ref "C25") (pin "1") (pinfunction "1_1") (pintype "passive"))
      (node (ref "C28") (pin "1") (pinfunction "1_1") (pintype "passive"))
      (node (ref "C3") (pin "1") (pinfunction "1_1") (pintype "passive"))
      (node (ref "C7") (pin "1") (pinfunction "1_1") (pintype "passive"))
      (node (ref "D4") (pin "1") (pinfunction "K_1") (pintype "passive"))
      (node (ref "D5") (pin "1") (pinfunction "K_1") (pintype "passive"))
      (node (ref "D6") (pin "1") (pinfunction "K_1") (pintype "passive"))
      (node (ref "J1") (pin "1") (pinfunction "1_1") (pintype "passive"))
      (node (ref "J1") (pin "2") (pinfunction "2_2") (pintype "passive"))
      (node (ref "J_PW") (pin "3") (pinfunction "Anode_3") (pintype "passive"))
      (node (ref "LDO2") (pin "3") (pinfunction "INPUT_3") (pintype "passive"))
      (node (ref "LS1") (pin "2") (pinfunction "+_2") (pintype "passive"))
      (node (ref "M1") (pin "9") (pinfunction "VCC_9") (pintype "passive"))
      (node (ref "P2") (pin "4") (pinfunction "4_4") (pintype "passive"))
      (node (ref "R10") (pin "2") (pinfunction "2_2") (pintype "passive"))
      (node (ref "R7") (pin "2") (pinfunction "2_2") (pintype "passive"))
    )
    (net (code "36") (name "DC7_5V") (class "Default")
      (node (ref "C13") (pin "1") (pinfunction "1_1") (pintype "passive"))
      (node (ref "C14") (pin "1") (pinfunction "1_1") (pintype "passive"))
      (node (ref "C15") (pin "1") (pinfunction "1_1") (pintype "passive"))
      (node (ref "C16") (pin "1") (pinfunction "1_1") (pintype "passive"))
      (node (ref "C30") (pin "1") (pinfunction "1_1") (pintype "passive"))
      (node (ref "CN1") (pin "3") (pinfunction "3_3") (pintype "passive"))
      (node (ref "D3") (pin "1") (pinfunction "K_1") (pintype "passive"))
      (node (ref "LDO3") (pin "2") (pinfunction "OUTPUT_1_2") (pintype "passive"))
      (node (ref "LDO3") (pin "4") (pinfunction "OUTPUT_2_4") (pintype "passive"))
      (node (ref "R5") (pin "1") (pinfunction "1_1") (pintype "passive"))
    )
    (net (code "37") (name "DC12V") (class "Default")
      (node (ref "C17") (pin "1") (pinfunction "1_1") (pintype "passive"))
      (node (ref "C24") (pin "1") (pinfunction "1_1") (pintype "passive"))
      (node (ref "C31") (pin "1") (pinfunction "1_1") (pintype "passive"))
      (node (ref "C32") (pin "1") (pinfunction "1_1") (pintype "passive"))
      (node (ref "C33") (pin "1") (pinfunction "1_1") (pintype "passive"))
      (node (ref "C34") (pin "1") (pinfunction "1_1") (pintype "passive"))
      (node (ref "C4") (pin "1") (pinfunction "1_1") (pintype "passive"))
      (node (ref "C5") (pin "1") (pinfunction "1_1") (pintype "passive"))
      (node (ref "CN_FAN") (pin "1") (pinfunction "1_1") (pintype "passive"))
      (node (ref "CN_HEATER") (pin "1") (pinfunction "1_1") (pintype "passive"))
      (node (ref "CN_HEATER") (pin "3") (pinfunction "3_3") (pintype "passive"))
      (node (ref "F1") (pin "2") (pinfunction "2_2") (pintype "passive"))
      (node (ref "LDO1") (pin "3") (pinfunction "INPUT_3") (pintype "passive"))
      (node (ref "LDO3") (pin "3") (pinfunction "INPUT_3") (pintype "passive"))
    )
    (net (code "38") (name "ESP_V3_3D") (class "Default")
      (node (ref "R11") (pin "2") (pinfunction "2_2") (pintype "passive"))
      (node (ref "R12") (pin "2") (pinfunction "2_2") (pintype "passive"))
      (node (ref "U2") (pin "2") (pinfunction "3V3_2") (pintype "power_in"))
    )
    (net (code "39") (name "FG") (class "Default")
      (node (ref "C29") (pin "1") (pinfunction "1_1") (pintype "passive"))
      (node (ref "CN_USB") (pin "SH1") (pinfunction "SHELL_GND_SH1") (pintype "power_in"))
      (node (ref "CN_USB") (pin "SH2") (pinfunction "SHELL_GND_SH2") (pintype "power_in"))
      (node (ref "CN_USB") (pin "SH3") (pinfunction "SHELL_GND_SH3") (pintype "power_in"))
      (node (ref "CN_USB") (pin "SH4") (pinfunction "SHELL_GND_SH4") (pintype "power_in"))
      (node (ref "H1") (pin "1") (pinfunction "1_1") (pintype "passive"))
      (node (ref "H2") (pin "1") (pinfunction "1_1") (pintype "passive"))
      (node (ref "H3") (pin "1") (pinfunction "1_1") (pintype "passive"))
      (node (ref "H4") (pin "1") (pinfunction "1_1") (pintype "passive"))
      (node (ref "R24") (pin "1") (pinfunction "1_1") (pintype "passive"))
    )
    (net (code "40") (name "GND") (class "Default")
      (node (ref "C1") (pin "2") (pinfunction "2_2") (pintype "passive"))
      (node (ref "C10") (pin "2") (pinfunction "2_2") (pintype "passive"))
      (node (ref "C11") (pin "2") (pinfunction "2_2") (pintype "passive"))
      (node (ref "C12") (pin "2") (pinfunction "2_2") (pintype "passive"))
      (node (ref "C13") (pin "2") (pinfunction "2_2") (pintype "passive"))
      (node (ref "C14") (pin "2") (pinfunction "2_2") (pintype "passive"))
      (node (ref "C15") (pin "2") (pinfunction "2_2") (pintype "passive"))
      (node (ref "C16") (pin "2") (pinfunction "2_2") (pintype "passive"))
      (node (ref "C17") (pin "2") (pinfunction "2_2") (pintype "passive"))
      (node (ref "C18") (pin "2") (pinfunction "2_2") (pintype "passive"))
      (node (ref "C19") (pin "2") (pinfunction "2_2") (pintype "passive"))
      (node (ref "C2") (pin "2") (pinfunction "2_2") (pintype "passive"))
      (node (ref "C20") (pin "2") (pinfunction "2_2") (pintype "passive"))
      (node (ref "C21") (pin "2") (pinfunction "2_2") (pintype "passive"))
      (node (ref "C22") (pin "1") (pinfunction "1_1") (pintype "passive"))
      (node (ref "C23") (pin "2") (pinfunction "2_2") (pintype "passive"))
      (node (ref "C24") (pin "2") (pinfunction "2_2") (pintype "passive"))
      (node (ref "C25") (pin "2") (pinfunction "2_2") (pintype "passive"))
      (node (ref "C26") (pin "2") (pinfunction "2_2") (pintype "passive"))
      (node (ref "C27") (pin "2") (pinfunction "2_2") (pintype "passive"))
      (node (ref "C28") (pin "2") (pinfunction "2_2") (pintype "passive"))
      (node (ref "C29") (pin "2") (pinfunction "2_2") (pintype "passive"))
      (node (ref "C3") (pin "2") (pinfunction "2_2") (pintype "passive"))
      (node (ref "C30") (pin "2") (pinfunction "2_2") (pintype "passive"))
      (node (ref "C31") (pin "2") (pinfunction "2_2") (pintype "passive"))
      (node (ref "C32") (pin "2") (pinfunction "2_2") (pintype "passive"))
      (node (ref "C33") (pin "2") (pinfunction "2_2") (pintype "passive"))
      (node (ref "C34") (pin "2") (pinfunction "2_2") (pintype "passive"))
      (node (ref "C4") (pin "2") (pinfunction "2_2") (pintype "passive"))
      (node (ref "C5") (pin "2") (pinfunction "2_2") (pintype "passive"))
      (node (ref "C6") (pin "2") (pinfunction "2_2") (pintype "passive"))
      (node (ref "C7") (pin "2") (pinfunction "2_2") (pintype "passive"))
      (node (ref "C8") (pin "2") (pinfunction "2_2") (pintype "passive"))
      (node (ref "C9") (pin "2") (pinfunction "2_2") (pintype "passive"))
      (node (ref "CN1") (pin "9") (pinfunction "9_9") (pintype "passive"))
      (node (ref "CN_COVER") (pin "3") (pinfunction "3_3") (pintype "passive"))
      (node (ref "CN_NTC") (pin "2") (pinfunction "2_2") (pintype "passive"))
      (node (ref "CN_USB") (pin "A1_B12") (pinfunction "GND_A1_B12") (pintype "power_in"))
      (node (ref "CN_USB") (pin "B1_A12") (pinfunction "GND_B1_A12") (pintype "power_in"))
      (node (ref "J1") (pin "16") (pinfunction "16_16") (pintype "passive"))
      (node (ref "J1") (pin "20") (pinfunction "20_20") (pintype "passive"))
      (node (ref "J1") (pin "3") (pinfunction "3_3") (pintype "passive"))
      (node (ref "J1") (pin "4") (pinfunction "4_4") (pintype "passive"))
      (node (ref "J1") (pin "MP1") (pinfunction "MP1_MP1") (pintype "passive"))
      (node (ref "J1") (pin "MP2") (pinfunction "MP2_MP2") (pintype "passive"))
      (node (ref "J2") (pin "2") (pinfunction "GND_1_2") (pintype "passive"))
      (node (ref "J2") (pin "3") (pinfunction "GND_2_3") (pintype "passive"))
      (node (ref "J3") (pin "6") (pinfunction "VSS_6") (pintype "passive"))
      (node (ref "J3") (pin "G1") (pinfunction "GROUND_G1") (pintype "passive"))
      (node (ref "J3") (pin "MP1") (pinfunction "MP1_MP1") (pintype "passive"))
      (node (ref "J3") (pin "MP2") (pinfunction "MP2_MP2") (pintype "passive"))
      (node (ref "J3") (pin "MP3") (pinfunction "MP3_MP3") (pintype "passive"))
      (node (ref "J4") (pin "10") (pinfunction "10_10") (pintype "passive"))
      (node (ref "J4") (pin "5") (pinfunction "5_5") (pintype "passive"))
      (node (ref "J4") (pin "MP1") (pinfunction "MP1_MP1") (pintype "passive"))
      (node (ref "J4") (pin "MP2") (pinfunction "MP2_MP2") (pintype "passive"))
      (node (ref "LED1") (pin "1") (pinfunction "CATHODE_1") (pintype "passive"))
      (node (ref "M1") (pin "8") (pinfunction "GND_8") (pintype "passive"))
      (node (ref "P2") (pin "5") (pinfunction "5_5") (pintype "passive"))
      (node (ref "Q3") (pin "3") (pinfunction "S_3") (pintype "passive"))
      (node (ref "Q4") (pin "3") (pinfunction "S_3") (pintype "passive"))
      (node (ref "Q5") (pin "2") (pinfunction "S_2") (pintype "passive"))
      (node (ref "R18") (pin "2") (pinfunction "2_2") (pintype "passive"))
      (node (ref "R19") (pin "2") (pinfunction "2_2") (pintype "passive"))
      (node (ref "R2") (pin "2") (pinfunction "2_2") (pintype "passive"))
      (node (ref "R24") (pin "2") (pinfunction "2_2") (pintype "passive"))
      (node (ref "R25") (pin "1") (pinfunction "1_1") (pintype "passive"))
      (node (ref "R28") (pin "2") (pinfunction "2_2") (pintype "passive"))
      (node (ref "R4") (pin "2") (pinfunction "2_2") (pintype "passive"))
      (node (ref "R8") (pin "2") (pinfunction "2_2") (pintype "passive"))
      (node (ref "Rd1") (pin "2") (pinfunction "2_2") (pintype "passive"))
      (node (ref "Rd2") (pin "2") (pinfunction "2_2") (pintype "passive"))
      (node (ref "SW_BOOT") (pin "2") (pinfunction "NO_1_2") (pintype "passive"))
      (node (ref "SW_RST") (pin "1") (pinfunction "COM_1_1") (pintype "passive"))
      (node (ref "U2") (pin "1") (pinfunction "GND_1") (pintype "power_in"))
      (node (ref "U2") (pin "40") (pinfunction "GND_40") (pintype "passive"))
      (node (ref "U2") (pin "41") (pinfunction "GND_41") (pintype "passive"))
      (node (ref "U3") (pin "5") (pinfunction "GND_5") (pintype "passive"))
    )
    (net (code "41") (name "Net-(D1-A)") (class "Default")
      (node (ref "C6") (pin "1") (pinfunction "1_1") (pintype "passive"))
      (node (ref "D1") (pin "2") (pinfunction "A_2") (pintype "passive"))
      (node (ref "LDO1") (pin "1") (pinfunction "ADJUST_1") (pintype "passive"))
      (node (ref "R1") (pin "2") (pinfunction "2_2") (pintype "passive"))
      (node (ref "R2") (pin "1") (pinfunction "1_1") (pintype "passive"))
    )
    (net (code "42") (name "Net-(D1-K)") (class "Default")
      (node (ref "D1") (pin "1") (pinfunction "K_1") (pintype "passive"))
      (node (ref "D6") (pin "2") (pinfunction "A_2") (pintype "passive"))
      (node (ref "LDO1") (pin "2") (pinfunction "OUTPUT_1_2") (pintype "passive"))
      (node (ref "LDO1") (pin "4") (pinfunction "OUTPUT_2_4") (pintype "passive"))
      (node (ref "R1") (pin "1") (pinfunction "1_1") (pintype "passive"))
    )
    (net (code "43") (name "Net-(D2-A)") (class "Default")
      (node (ref "C12") (pin "1") (pinfunction "1_1") (pintype "passive"))
      (node (ref "D2") (pin "2") (pinfunction "A_2") (pintype "passive"))
      (node (ref "LDO2") (pin "1") (pinfunction "ADJUST_1") (pintype "passive"))
      (node (ref "R3") (pin "2") (pinfunction "2_2") (pintype "passive"))
      (node (ref "R4") (pin "1") (pinfunction "1_1") (pintype "passive"))
    )
    (net (code "44") (name "Net-(D3-A)") (class "Default")
      (node (ref "C18") (pin "1") (pinfunction "1_1") (pintype "passive"))
      (node (ref "D3") (pin "2") (pinfunction "A_2") (pintype "passive"))
      (node (ref "LDO3") (pin "1") (pinfunction "ADJUST_1") (pintype "passive"))
      (node (ref "R5") (pin "2") (pinfunction "2_2") (pintype "passive"))
      (node (ref "R8") (pin "1") (pinfunction "1_1") (pintype "passive"))
    )
    (net (code "45") (name "Net-(D4-A)") (class "Default")
      (node (ref "D4") (pin "2") (pinfunction "A_2") (pintype "passive"))
      (node (ref "U3") (pin "1") (pinfunction "VCC_1") (pintype "passive"))
    )
    (net (code "46") (name "Net-(D5-A)") (class "Default")
      (node (ref "D5") (pin "2") (pinfunction "A_2") (pintype "passive"))
      (node (ref "LS1") (pin "1") (pinfunction "-_1") (pintype "passive"))
      (node (ref "Q5") (pin "3") (pinfunction "D_3") (pintype "passive"))
    )
    (net (code "47") (name "Net-(J3-CARD_DETECTION)") (class "Default")
      (node (ref "J3") (pin "CD1") (pinfunction "CARD_DETECTION_CD1") (pintype "passive"))
      (node (ref "T11") (pin "1") (pinfunction "T_1") (pintype "passive"))
    )
    (net (code "48") (name "Net-(J3-DAT0)") (class "Default")
      (node (ref "J3") (pin "7") (pinfunction "DAT0_7") (pintype "passive"))
      (node (ref "R14") (pin "1") (pinfunction "1_1") (pintype "passive"))
    )
    (net (code "49") (name "Net-(J3-DAT1)") (class "Default")
      (node (ref "J3") (pin "8") (pinfunction "DAT1_8") (pintype "passive"))
      (node (ref "T9") (pin "1") (pinfunction "T_1") (pintype "passive"))
    )
    (net (code "50") (name "Net-(J3-DAT2)") (class "Default")
      (node (ref "J3") (pin "1") (pinfunction "DAT2_1") (pintype "passive"))
      (node (ref "T8") (pin "1") (pinfunction "T_1") (pintype "passive"))
    )
    (net (code "51") (name "Net-(J_PW-Cathode)") (class "Default")
      (node (ref "J_PW") (pin "4") (pinfunction "Cathode_4") (pintype "passive"))
      (node (ref "R28") (pin "1") (pinfunction "1_1") (pintype "passive"))
    )
    (net (code "52") (name "Net-(LED1-ANODE)") (class "Default")
      (node (ref "LED1") (pin "2") (pinfunction "ANODE_2") (pintype "passive"))
      (node (ref "R15") (pin "1") (pinfunction "1_1") (pintype "passive"))
    )
    (net (code "53") (name "Net-(M1-BAT)") (class "Default")
      (node (ref "M1") (pin "7") (pinfunction "BAT_7") (pintype "passive"))
      (node (ref "P1") (pin "7") (pinfunction "7_7") (pintype "passive"))
    )
    (net (code "54") (name "Net-(M1-DS-Pad2)") (class "Default")
      (node (ref "M1") (pin "2") (pinfunction "DS_2") (pintype "passive"))
      (node (ref "P1") (pin "2") (pinfunction "2_2") (pintype "passive"))
    )
    (net (code "55") (name "Net-(M1-DS-Pad12)") (class "Default")
      (node (ref "M1") (pin "12") (pinfunction "DS_12") (pintype "passive"))
      (node (ref "P2") (pin "1") (pinfunction "1_1") (pintype "passive"))
    )
    (net (code "56") (name "Net-(M1-GND-Pad6)") (class "Default")
      (node (ref "M1") (pin "6") (pinfunction "GND_6") (pintype "passive"))
      (node (ref "P1") (pin "6") (pinfunction "6_6") (pintype "passive"))
    )
    (net (code "57") (name "Net-(M1-SCL-Pad3)") (class "Default")
      (node (ref "M1") (pin "3") (pinfunction "SCL_3") (pintype "passive"))
      (node (ref "P1") (pin "3") (pinfunction "3_3") (pintype "passive"))
    )
    (net (code "58") (name "Net-(M1-SDA-Pad4)") (class "Default")
      (node (ref "M1") (pin "4") (pinfunction "SDA_4") (pintype "passive"))
      (node (ref "P1") (pin "4") (pinfunction "4_4") (pintype "passive"))
    )
    (net (code "59") (name "Net-(M1-SQ)") (class "Default")
      (node (ref "M1") (pin "1") (pinfunction "SQ_1") (pintype "passive"))
      (node (ref "P1") (pin "1") (pinfunction "1_1") (pintype "passive"))
    )
    (net (code "60") (name "Net-(M1-VCC-Pad5)") (class "Default")
      (node (ref "M1") (pin "5") (pinfunction "VCC_5") (pintype "passive"))
      (node (ref "P1") (pin "5") (pinfunction "5_5") (pintype "passive"))
    )
    (net (code "61") (name "Net-(Q3-D_NOPAD)") (class "Default")
      (node (ref "CN_FAN") (pin "2") (pinfunction "2_2") (pintype "passive"))
      (node (ref "Q3") (pin "2") (pinfunction "D_NOPAD_2") (pintype "passive"))
      (node (ref "Q3") (pin "4") (pinfunction "D_TAB_4") (pintype "passive"))
    )
    (net (code "62") (name "Net-(Q3-G)") (class "Default")
      (node (ref "Q3") (pin "1") (pinfunction "G_1") (pintype "passive"))
      (node (ref "R18") (pin "1") (pinfunction "1_1") (pintype "passive"))
      (node (ref "R29") (pin "1") (pinfunction "1_1") (pintype "passive"))
    )
    (net (code "63") (name "Net-(Q4-D_NOPAD)") (class "Default")
      (node (ref "CN_HEATER") (pin "2") (pinfunction "2_2") (pintype "passive"))
      (node (ref "CN_HEATER") (pin "4") (pinfunction "4_4") (pintype "passive"))
      (node (ref "Q4") (pin "2") (pinfunction "D_NOPAD_2") (pintype "passive"))
      (node (ref "Q4") (pin "4") (pinfunction "D_TAB_4") (pintype "passive"))
    )
    (net (code "64") (name "Net-(Q4-G)") (class "Default")
      (node (ref "Q4") (pin "1") (pinfunction "G_1") (pintype "passive"))
      (node (ref "R19") (pin "1") (pinfunction "1_1") (pintype "passive"))
      (node (ref "R30") (pin "1") (pinfunction "1_1") (pintype "passive"))
    )
    (net (code "65") (name "Net-(Q5-G)") (class "Default")
      (node (ref "Q5") (pin "1") (pinfunction "G_1") (pintype "passive"))
      (node (ref "R23") (pin "1") (pinfunction "1_1") (pintype "passive"))
      (node (ref "R25") (pin "2") (pinfunction "2_2") (pintype "passive"))
    )
    (net (code "66") (name "Net-(R23-Pad2)") (class "Default")
      (node (ref "R23") (pin "2") (pinfunction "2_2") (pintype "passive"))
      (node (ref "R26") (pin "1") (pinfunction "1_1") (pintype "passive"))
      (node (ref "R27") (pin "1") (pinfunction "1_1") (pintype "passive"))
    )
    (net (code "67") (name "Net-(SW_BOOT-COM_1)") (class "Default")
      (node (ref "SW_BOOT") (pin "1") (pinfunction "COM_1_1") (pintype "passive"))
      (node (ref "U2") (pin "27") (pinfunction "GPIO0/BOOT_27") (pintype "bidirectional"))
    )
    (net (code "68") (name "Net-(T6-T)") (class "Default")
      (node (ref "T6") (pin "1") (pinfunction "T_1") (pintype "passive"))
      (node (ref "U2") (pin "37") (pinfunction "U0TXD/GPIO43/CLK_OUT1_37") (pintype "bidirectional"))
    )
    (net (code "69") (name "Net-(T7-T)") (class "Default")
      (node (ref "T7") (pin "1") (pinfunction "T_1") (pintype "passive"))
      (node (ref "U2") (pin "36") (pinfunction "U0RXD/GPIO44/CLK_OUT2_36") (pintype "bidirectional"))
    )
    (net (code "70") (name "Net-(T10-T)") (class "Default")
      (node (ref "T10") (pin "1") (pinfunction "T_1") (pintype "passive"))
      (node (ref "U2") (pin "15") (pinfunction "GPIO3/TOUCH3/ADC1_CH2_15") (pintype "bidirectional"))
    )
    (net (code "71") (name "Net-(T12-T)") (class "Default")
      (node (ref "T12") (pin "1") (pinfunction "T_1") (pintype "passive"))
      (node (ref "U2") (pin "26") (pinfunction "GPIO45_26") (pintype "bidirectional"))
    )
    (net (code "72") (name "Net-(T13-T)") (class "Default")
      (node (ref "T13") (pin "1") (pinfunction "T_1") (pintype "passive"))
      (node (ref "U2") (pin "16") (pinfunction "GPIO46_16") (pintype "bidirectional"))
    )
    (net (code "73") (name "Net-(T15-T)") (class "Default")
      (node (ref "T15") (pin "1") (pinfunction "T_1") (pintype "passive"))
      (node (ref "U2") (pin "39") (pinfunction "GPIO1/TOUCH1/ADC1_CH0_39") (pintype "bidirectional"))
    )
    (net (code "74") (name "Net-(T16-T)") (class "Default")
      (node (ref "T16") (pin "1") (pinfunction "T_1") (pintype "passive"))
      (node (ref "U2") (pin "38") (pinfunction "GPIO2/TOUCH2/ADC1_CH1_38") (pintype "bidirectional"))
    )
    (net (code "75") (name "Net-(T17-T)") (class "Default")
      (node (ref "T17") (pin "1") (pinfunction "T_1") (pintype "passive"))
      (node (ref "U2") (pin "22") (pinfunction "GPIO14/TOUCH14/ADC2_CH3/FSPIWP/FSPIDQS/SUBSPIWP_22") (pintype "bidirectional"))
    )
    (net (code "76") (name "Net-(T18-T)") (class "Default")
      (node (ref "T18") (pin "1") (pinfunction "T_1") (pintype "passive"))
      (node (ref "U2") (pin "10") (pinfunction "GPIO17/U1TXD/ADC2_CH6_10") (pintype "bidirectional"))
    )
    (net (code "77") (name "Net-(U2-GPIO38{slash}FSPIWP{slash}SUBSPIWP)") (class "Default")
      (node (ref "R16") (pin "2") (pinfunction "2_2") (pintype "passive"))
      (node (ref "U2") (pin "31") (pinfunction "GPIO38/FSPIWP/SUBSPIWP_31") (pintype "bidirectional"))
    )
    (net (code "78") (name "Net-(U2-MTCK{slash}GPIO39{slash}CLK_OUT3{slash}SUBSPICS1)") (class "Default")
      (node (ref "R13") (pin "1") (pinfunction "1_1") (pintype "passive"))
      (node (ref "U2") (pin "32") (pinfunction "MTCK/GPIO39/CLK_OUT3/SUBSPICS1_32") (pintype "bidirectional"))
    )
    (net (code "79") (name "Net-(U2-MTDI{slash}GPIO41{slash}CLK_OUT1)") (class "Default")
      (node (ref "R15") (pin "2") (pinfunction "2_2") (pintype "passive"))
      (node (ref "U2") (pin "34") (pinfunction "MTDI/GPIO41/CLK_OUT1_34") (pintype "bidirectional"))
    )
    (net (code "80") (name "Net-(U2-SPIIO7{slash}GPIO36{slash}FSPICLK{slash}SUBSPICLK)") (class "Default")
      (node (ref "R17") (pin "1") (pinfunction "1_1") (pintype "passive"))
      (node (ref "U2") (pin "29") (pinfunction "SPIIO7/GPIO36/FSPICLK/SUBSPICLK_29") (pintype "bidirectional"))
    )
    (net (code "81") (name "V3_3D") (class "Default")
      (node (ref "C10") (pin "1") (pinfunction "1_1") (pintype "passive"))
      (node (ref "C20") (pin "1") (pinfunction "1_1") (pintype "passive"))
      (node (ref "C21") (pin "1") (pinfunction "1_1") (pintype "passive"))
      (node (ref "C23") (pin "1") (pinfunction "1_1") (pintype "passive"))
      (node (ref "C26") (pin "1") (pinfunction "1_1") (pintype "passive"))
      (node (ref "C27") (pin "1") (pinfunction "1_1") (pintype "passive"))
      (node (ref "C8") (pin "1") (pinfunction "1_1") (pintype "passive"))
      (node (ref "C9") (pin "1") (pinfunction "1_1") (pintype "passive"))
      (node (ref "CN_COVER") (pin "2") (pinfunction "2_2") (pintype "passive"))
      (node (ref "D2") (pin "1") (pinfunction "K_1") (pintype "passive"))
      (node (ref "J3") (pin "4") (pinfunction "VDD_4") (pintype "passive"))
      (node (ref "J4") (pin "11") (pinfunction "11_11") (pintype "passive"))
      (node (ref "LDO2") (pin "2") (pinfunction "OUTPUT_1_2") (pintype "passive"))
      (node (ref "LDO2") (pin "4") (pinfunction "OUTPUT_2_4") (pintype "passive"))
      (node (ref "Q1") (pin "1") (pinfunction "G_1") (pintype "passive"))
      (node (ref "Q2") (pin "1") (pinfunction "G_1") (pintype "passive"))
      (node (ref "R11") (pin "1") (pinfunction "1_1") (pintype "passive"))
      (node (ref "R20") (pin "1") (pinfunction "1_1") (pintype "passive"))
      (node (ref "R21") (pin "2") (pinfunction "2_2") (pintype "passive"))
      (node (ref "R22") (pin "2") (pinfunction "2_2") (pintype "passive"))
      (node (ref "R3") (pin "1") (pinfunction "1_1") (pintype "passive"))
      (node (ref "R6") (pin "2") (pinfunction "2_2") (pintype "passive"))
      (node (ref "R9") (pin "2") (pinfunction "2_2") (pintype "passive"))
    )
    (net (code "82") (name "VIN12V") (class "Default")
      (node (ref "F1") (pin "1") (pinfunction "1_1") (pintype "passive"))
      (node (ref "J_PW") (pin "2") (pinfunction "NO_2") (pintype "passive"))
    )
    (net (code "83") (name "VUSB") (class "Default")
      (node (ref "CN_USB") (pin "A4_B9") (pinfunction "VBUS_A4_B9") (pintype "power_in"))
      (node (ref "CN_USB") (pin "B4_A9") (pinfunction "VBUS_B4_A9") (pintype "power_in"))
      (node (ref "U3") (pin "8") (pinfunction "VCC_8") (pintype "passive"))
    )
    (net (code "84") (name "unconnected-(CN1-Pad1)") (class "Default")
      (node (ref "CN1") (pin "1") (pinfunction "1_1") (pintype "passive"))
    )
    (net (code "85") (name "unconnected-(CN1-Pad2)") (class "Default")
      (node (ref "CN1") (pin "2") (pinfunction "2_2") (pintype "passive"))
    )
    (net (code "86") (name "unconnected-(CN_COVER-Pad4)") (class "Default")
      (node (ref "CN_COVER") (pin "4") (pinfunction "4_4") (pintype "passive+no_connect"))
    )
    (net (code "87") (name "unconnected-(CN_USB-SBU1-PadA8)") (class "Default")
      (node (ref "CN_USB") (pin "A8") (pinfunction "SBU1_A8") (pintype "bidirectional+no_connect"))
    )
    (net (code "88") (name "unconnected-(CN_USB-SBU2-PadB8)") (class "Default")
      (node (ref "CN_USB") (pin "B8") (pinfunction "SBU2_B8") (pintype "bidirectional+no_connect"))
    )
    (net (code "89") (name "unconnected-(J1-Pad15)") (class "Default")
      (node (ref "J1") (pin "15") (pinfunction "15_15") (pintype "passive+no_connect"))
    )
    (net (code "90") (name "unconnected-(J1-Pad17)") (class "Default")
      (node (ref "J1") (pin "17") (pinfunction "17_17") (pintype "passive+no_connect"))
    )
    (net (code "91") (name "unconnected-(J1-Pad18)") (class "Default")
      (node (ref "J1") (pin "18") (pinfunction "18_18") (pintype "passive+no_connect"))
    )
    (net (code "92") (name "unconnected-(J1-Pad19)") (class "Default")
      (node (ref "J1") (pin "19") (pinfunction "19_19") (pintype "passive+no_connect"))
    )
    (net (code "93") (name "unconnected-(J4-Pad2)") (class "Default")
      (node (ref "J4") (pin "2") (pinfunction "2_2") (pintype "passive+no_connect"))
    )
    (net (code "94") (name "unconnected-(J4-Pad3)") (class "Default")
      (node (ref "J4") (pin "3") (pinfunction "3_3") (pintype "passive+no_connect"))
    )
    (net (code "95") (name "unconnected-(J4-Pad6)") (class "Default")
      (node (ref "J4") (pin "6") (pinfunction "6_6") (pintype "passive+no_connect"))
    )
    (net (code "96") (name "unconnected-(J4-Pad7)") (class "Default")
      (node (ref "J4") (pin "7") (pinfunction "7_7") (pintype "passive+no_connect"))
    )
    (net (code "97") (name "unconnected-(J4-Pad12)") (class "Default")
      (node (ref "J4") (pin "12") (pinfunction "12_12") (pintype "passive+no_connect"))
    )
    (net (code "98") (name "unconnected-(SW_PW-Anode-Pad3)") (class "Default")
      (node (ref "SW_PW") (pin "3") (pinfunction "Anode_3") (pintype "passive+no_connect"))
    )
    (net (code "99") (name "unconnected-(SW_PW-COM-Pad1)") (class "Default")
      (node (ref "SW_PW") (pin "1") (pinfunction "COM_1") (pintype "passive+no_connect"))
    )
    (net (code "100") (name "unconnected-(SW_PW-Cathode-Pad4)") (class "Default")
      (node (ref "SW_PW") (pin "4") (pinfunction "Cathode_4") (pintype "passive+no_connect"))
    )
    (net (code "101") (name "unconnected-(SW_PW-NO-Pad2)") (class "Default")
      (node (ref "SW_PW") (pin "2") (pinfunction "NO_2") (pintype "passive+no_connect"))
    )
    (net (code "102") (name "unconnected-(U3-GND-Pad4)") (class "Default")
      (node (ref "U3") (pin "4") (pinfunction "GND_4") (pintype "passive+no_connect"))
    )
  )
)
